# PUSH_BUTTONs_INTERFACE.net
KiCad netlist of a schematic drawn in Altium Designer
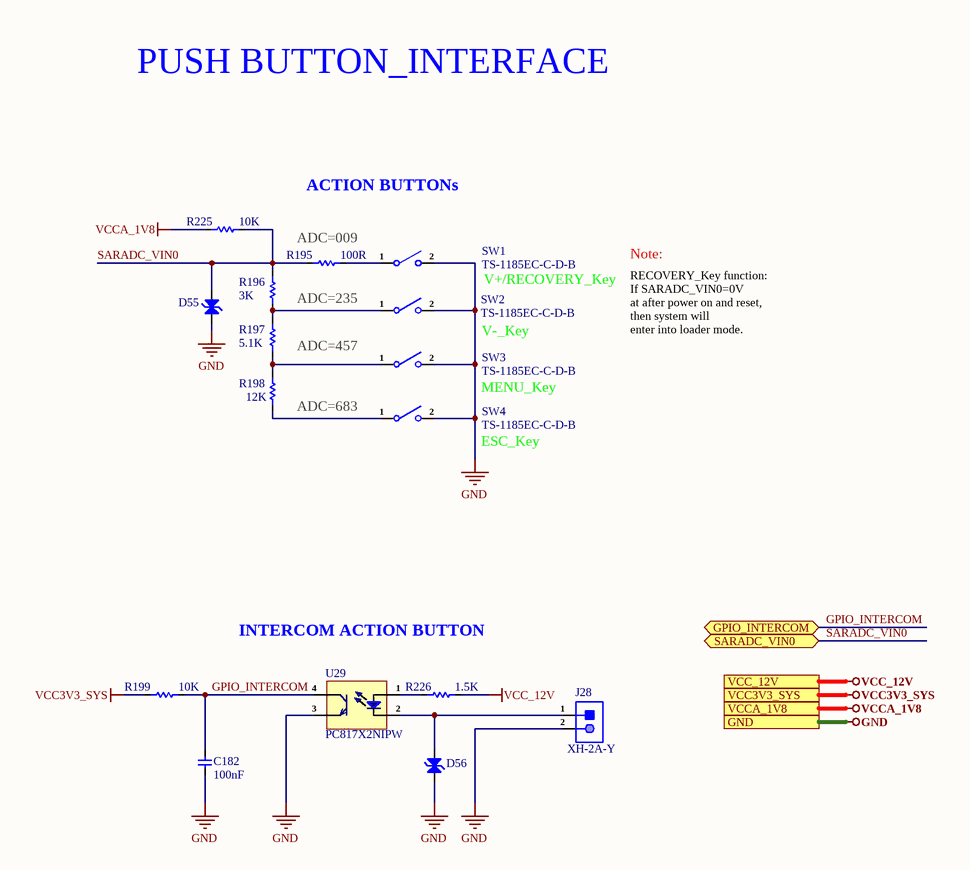
[diagram p0: PUSH BUTTONs_INTERFACE.SchDoc]

(export (version "E")
  (design (tool "Eeschema 10.0.6"))
  (components
    (comp (ref "C182")
      (value "100nF")
      (footprint "Cap-0402")
      (description "CAP CER 0.1UF 16V X5R 0402")
      (fields
        (field (name "MANUFACTURER") "Yageo")
        (field (name "MANUFACTURER PART NUMBER") "CC0402KRX5R7BB104")
      )
      (libsource (lib "eSpark Libraries") (part "CC0402KRX5R7BB104"))
    )
    (comp (ref "D55")
      (value "ESD5451N")
      (footprint "DFN1006-2L (Bi-Directional)")
      (description "DFN1006-2(0402) ESD Protection Devices ROHS")
      (fields (field (name "MANUFACTURER") "TECH PUBLIC") (field (name "LCSC PART NUMBER") "C2936977"))
      (libsource (lib "eSpark Libraries") (part "ESD5451N"))
    )
    (comp (ref "D56")
      (value "ESD5451N")
      (footprint "DFN1006-2L (Bi-Directional)")
      (description "DFN1006-2(0402) ESD Protection Devices ROHS")
      (fields (field (name "MANUFACTURER") "TECH PUBLIC") (field (name "LCSC PART NUMBER") "C2936977"))
      (libsource (lib "eSpark Libraries") (part "ESD5451N"))
    )
    (comp (ref "J28")
      (value "XH-2A-Y")
      (footprint "XH-2A-Y")
      (description "1x2P 2P XH 1 Tin 2.5mm 2 -25℃~+85℃ Brass 3A Straight Plugin,P=2.5mm Wire To Board Connector ROHS")
      (fields (field (name "MANUFACTURER") "HCTL") (field (name "LCSC PART NUMBER") "C2908595"))
      (libsource (lib "eSpark Libraries") (part "XH-2A-Y"))
    )
    (comp (ref "R195")
      (value "100R")
      (footprint "Res-0402")
      (description "RES 100 OHM 1% 1/16W 0402")
      (fields
        (field (name "MANUFACTURER") "Yageo")
        (field (name "MANUFACTURER PART NUMBER") "RC0402FR-07100RL")
      )
      (libsource (lib "eSpark Libraries") (part "RC0402FR-07100RL"))
    )
    (comp (ref "R196")
      (value "3K")
      (footprint "Res-0402")
      (description "RES 3K OHM 1% 1/16W 0402")
      (fields
        (field (name "MANUFACTURER") "Yageo")
        (field (name "MANUFACTURER PART NUMBER") "RC0402FR-073KL")
      )
      (libsource (lib "eSpark Libraries") (part "RC0402FR-073KL"))
    )
    (comp (ref "R197")
      (value "5.1K")
      (footprint "Res-0402")
      (description "RES 5.1K OHM 1% 1/16W 0402")
      (fields
        (field (name "MANUFACTURER") "Yageo")
        (field (name "MANUFACTURER PART NUMBER") "RC0402FR-075K1L")
      )
      (libsource (lib "eSpark Libraries") (part "RC0402FR-075K1L"))
    )
    (comp (ref "R198")
      (value "12K")
      (footprint "Res-0402")
      (description "RES 12K OHM 1% 1/16W 0402")
      (fields
        (field (name "MANUFACTURER") "Yageo")
        (field (name "MANUFACTURER PART NUMBER") "RC0402FR-0712KL")
      )
      (libsource (lib "eSpark Libraries") (part "RC0402FR-0712KL"))
    )
    (comp (ref "R199")
      (value "10K")
      (footprint "Res-0402")
      (description "RES 10K OHM 1% 1/16W 0402")
      (fields
        (field (name "MANUFACTURER") "Yageo")
        (field (name "MANUFACTURER PART NUMBER") "RC0402FR-0710KL")
      )
      (libsource (lib "eSpark Libraries") (part "RC0402FR-0710KL"))
    )
    (comp (ref "R225")
      (value "10K")
      (footprint "Res-0402")
      (description "RES 10K OHM 1% 1/16W 0402")
      (fields
        (field (name "MANUFACTURER") "Yageo")
        (field (name "MANUFACTURER PART NUMBER") "RC0402FR-0710KL")
      )
      (libsource (lib "eSpark Libraries") (part "RC0402FR-0710KL"))
    )
    (comp (ref "R226")
      (value "1.5K")
      (footprint "Res-0402")
      (description "RES 1.5K OHM 1% 1/16W 0402")
      (fields
        (field (name "MANUFACTURER") "Yageo")
        (field (name "MANUFACTURER PART NUMBER") "RC0402FR-071K5L")
      )
      (libsource (lib "eSpark Libraries") (part "RC0402FR-071K5L"))
    )
    (comp (ref "SW1")
      (value "TS-1185EC-C-D-B")
      (footprint "TS-1185EC-C-D-B_")
      (description "3mm 2mm Round Button 50mA Top3.65mm SPST 12V SMD Tactile Switches")
      (fields (field (name "MANUFACTURER") "XKB") (field (name "LCSC PART NUMBER") "C318893"))
      (libsource (lib "eSpark Libraries") (part "TS-1185EC-C-D-B"))
    )
    (comp (ref "SW2")
      (value "TS-1185EC-C-D-B")
      (footprint "TS-1185EC-C-D-B_")
      (description "3mm 2mm Round Button 50mA Top3.65mm SPST 12V SMD Tactile Switches")
      (fields (field (name "MANUFACTURER") "XKB") (field (name "LCSC PART NUMBER") "C318893"))
      (libsource (lib "eSpark Libraries") (part "TS-1185EC-C-D-B"))
    )
    (comp (ref "SW3")
      (value "TS-1185EC-C-D-B")
      (footprint "TS-1185EC-C-D-B_")
      (description "3mm 2mm Round Button 50mA Top3.65mm SPST 12V SMD Tactile Switches")
      (fields (field (name "MANUFACTURER") "XKB") (field (name "LCSC PART NUMBER") "C318893"))
      (libsource (lib "eSpark Libraries") (part "TS-1185EC-C-D-B"))
    )
    (comp (ref "SW4")
      (value "TS-1185EC-C-D-B")
      (footprint "TS-1185EC-C-D-B_")
      (description "3mm 2mm Round Button 50mA Top3.65mm SPST 12V SMD Tactile Switches")
      (fields (field (name "MANUFACTURER") "XKB") (field (name "LCSC PART NUMBER") "C318893"))
      (libsource (lib "eSpark Libraries") (part "TS-1185EC-C-D-B"))
    )
    (comp (ref "U29")
      (value "PC817X2NIPW")
      (footprint "PC817X2NIPW")
      (description "Optoisolator Output Channel 4-SMD")
      (fields (field (name "MANUFACTURER") "Sharp") (field (name "LCSC PART NUMBER") "C2840443"))
      (libsource (lib "eSpark Libraries") (part "PC817X2NIPW"))
    )
  )
  (nets
    (net (code "1") (name "/GPIO_INTERCOM") (class "Default")
      (node (ref "C182") (pin "2") (pinfunction "2_2") (pintype "passive"))
      (node (ref "R199") (pin "1") (pinfunction "1_1") (pintype "passive"))
      (node (ref "U29") (pin "4") (pinfunction "C_4") (pintype "passive"))
    )
    (net (code "2") (name "/SARADC_VIN0") (class "Default")
      (node (ref "D55") (pin "2") (pinfunction "K_2") (pintype "passive"))
      (node (ref "R195") (pin "1") (pinfunction "1_1") (pintype "passive"))
      (node (ref "R196") (pin "2") (pinfunction "2_2") (pintype "passive"))
      (node (ref "R225") (pin "1") (pinfunction "1_1") (pintype "passive"))
    )
    (net (code "3") (name "GND") (class "Default")
      (node (ref "C182") (pin "1") (pinfunction "1_1") (pintype "passive"))
      (node (ref "D55") (pin "1") (pinfunction "K_1") (pintype "passive"))
      (node (ref "D56") (pin "1") (pinfunction "K_1") (pintype "passive"))
      (node (ref "J28") (pin "2") (pinfunction "2_2") (pintype "passive"))
      (node (ref "SW1") (pin "2") (pinfunction "2_2") (pintype "passive"))
      (node (ref "SW2") (pin "2") (pinfunction "2_2") (pintype "passive"))
      (node (ref "SW3") (pin "2") (pinfunction "2_2") (pintype "passive"))
      (node (ref "SW4") (pin "2") (pinfunction "2_2") (pintype "passive"))
      (node (ref "U29") (pin "3") (pinfunction "E_3") (pintype "passive"))
    )
    (net (code "4") (name "Net-(R195-Pad2)") (class "Default")
      (node (ref "R195") (pin "2") (pinfunction "2_2") (pintype "passive"))
      (node (ref "SW1") (pin "1") (pinfunction "1_1") (pintype "passive"))
    )
    (net (code "5") (name "Net-(R196-Pad1)") (class "Default")
      (node (ref "R196") (pin "1") (pinfunction "1_1") (pintype "passive"))
      (node (ref "R197") (pin "2") (pinfunction "2_2") (pintype "passive"))
      (node (ref "SW2") (pin "1") (pinfunction "1_1") (pintype "passive"))
    )
    (net (code "6") (name "Net-(R197-Pad1)") (class "Default")
      (node (ref "R197") (pin "1") (pinfunction "1_1") (pintype "passive"))
      (node (ref "R198") (pin "2") (pinfunction "2_2") (pintype "passive"))
      (node (ref "SW3") (pin "1") (pinfunction "1_1") (pintype "passive"))
    )
    (net (code "7") (name "Net-(R198-Pad1)") (class "Default")
      (node (ref "R198") (pin "1") (pinfunction "1_1") (pintype "passive"))
      (node (ref "SW4") (pin "1") (pinfunction "1_1") (pintype "passive"))
    )
    (net (code "8") (name "Net-(U29-An)") (class "Default")
      (node (ref "R226") (pin "1") (pinfunction "1_1") (pintype "passive"))
      (node (ref "U29") (pin "1") (pinfunction "An_1") (pintype "passive"))
    )
    (net (code "9") (name "Net-(U29-Ca)") (class "Default")
      (node (ref "D56") (pin "2") (pinfunction "K_2") (pintype "passive"))
      (node (ref "J28") (pin "1") (pinfunction "1_1") (pintype "passive"))
      (node (ref "U29") (pin "2") (pinfunction "Ca_2") (pintype "passive"))
    )
    (net (code "10") (name "VCC3V3_SYS") (class "Default")
      (node (ref "R199") (pin "2") (pinfunction "2_2") (pintype "passive"))
    )
    (net (code "11") (name "VCCA_1V8") (class "Default")
      (node (ref "R225") (pin "2") (pinfunction "2_2") (pintype "passive"))
    )
    (net (code "12") (name "VCC_12V") (class "Default")
      (node (ref "R226") (pin "2") (pinfunction "2_2") (pintype "passive"))
    )
  )
)
